# InkTime.net
KiCad netlist of a schematic drawn in EAGLE
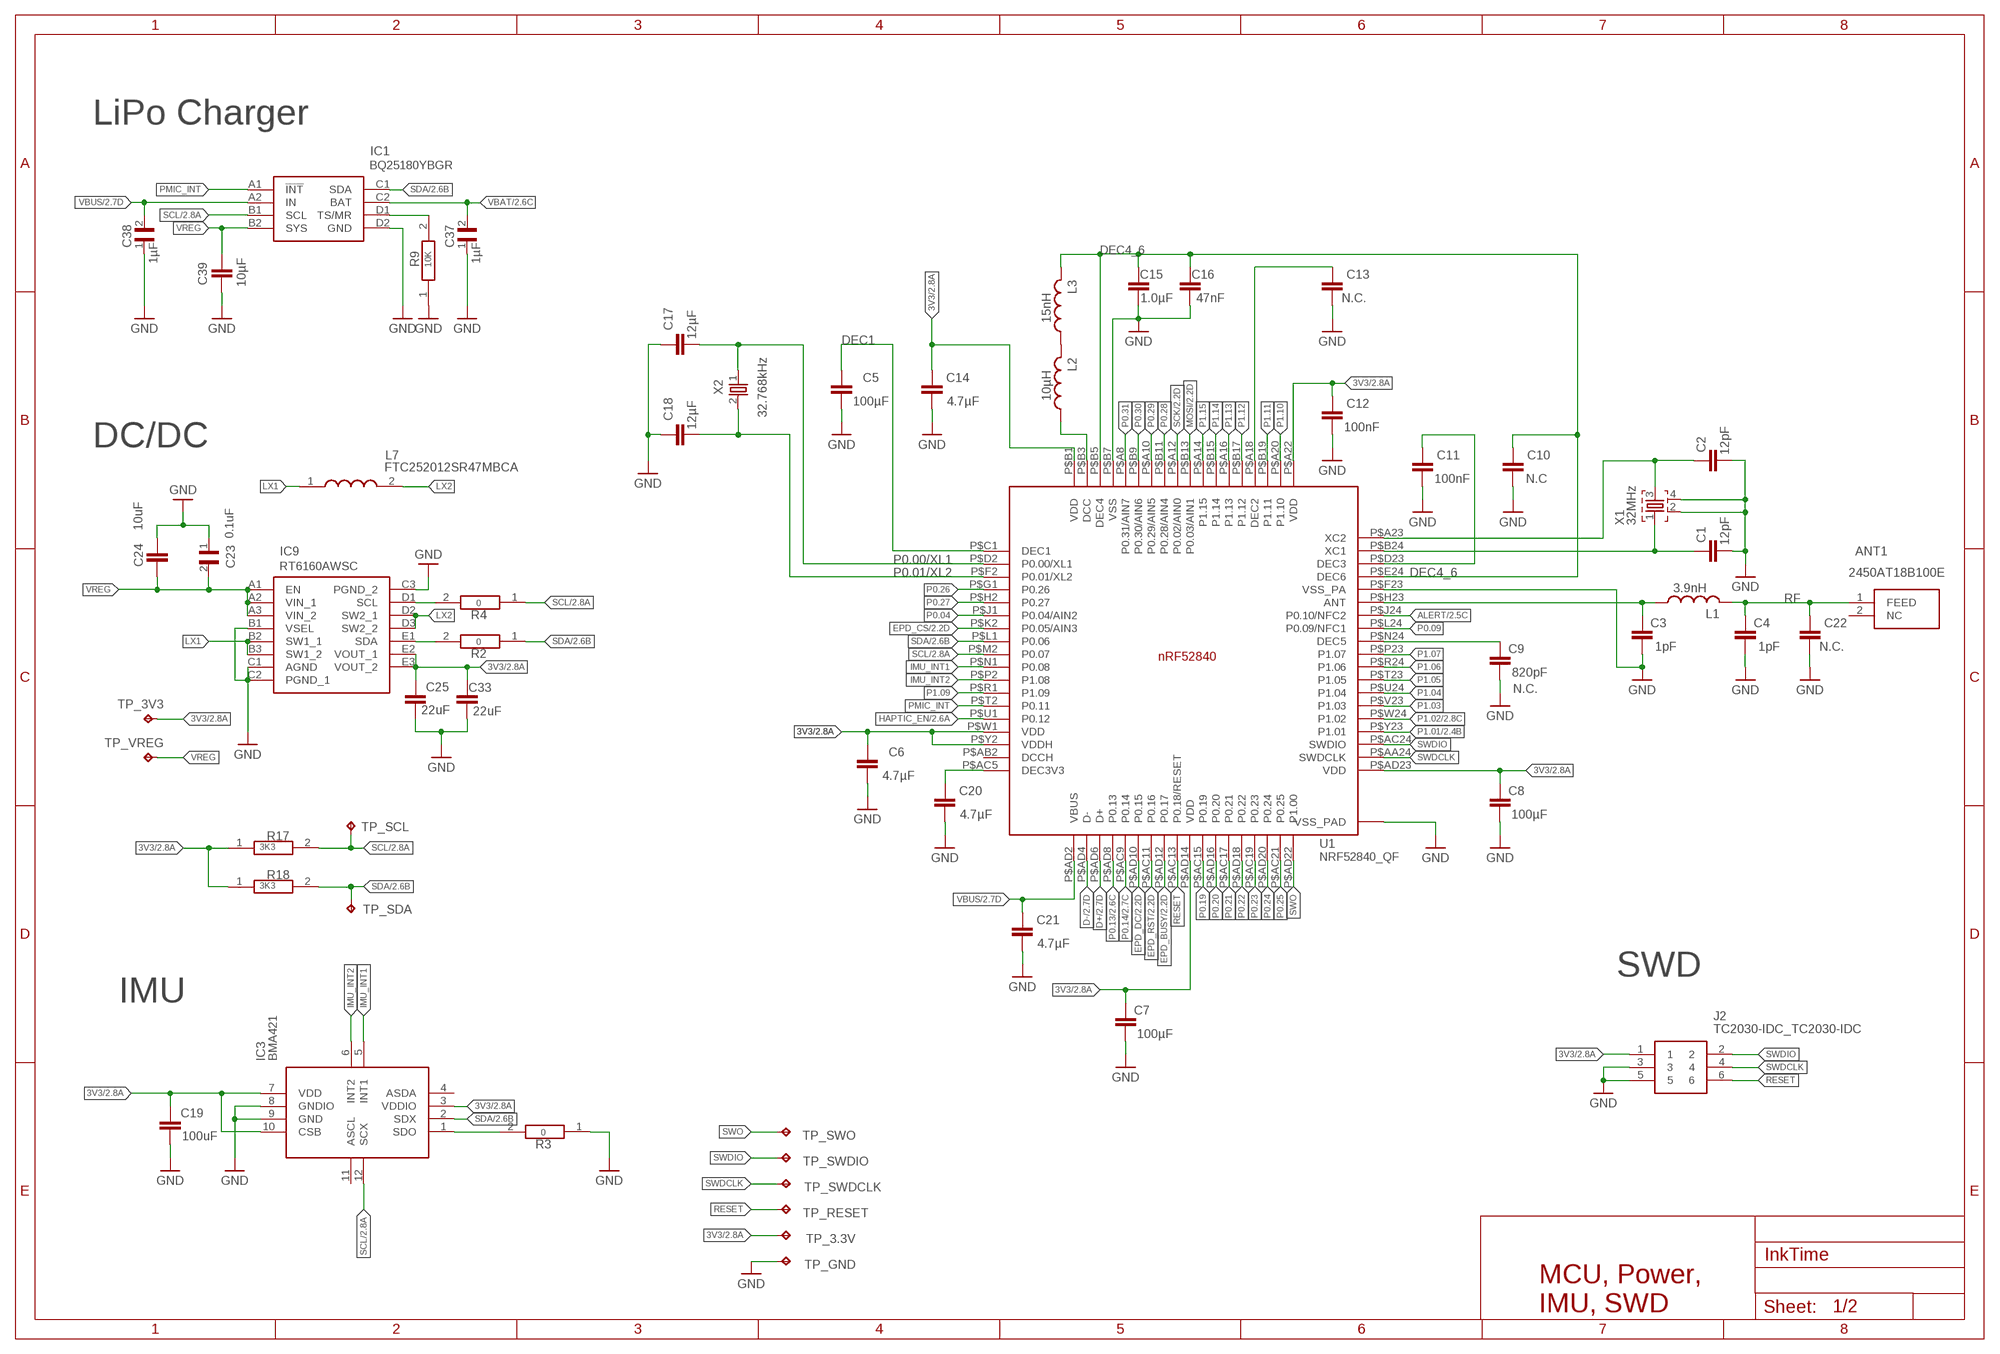
[diagram p0: schematic, sheet 1]
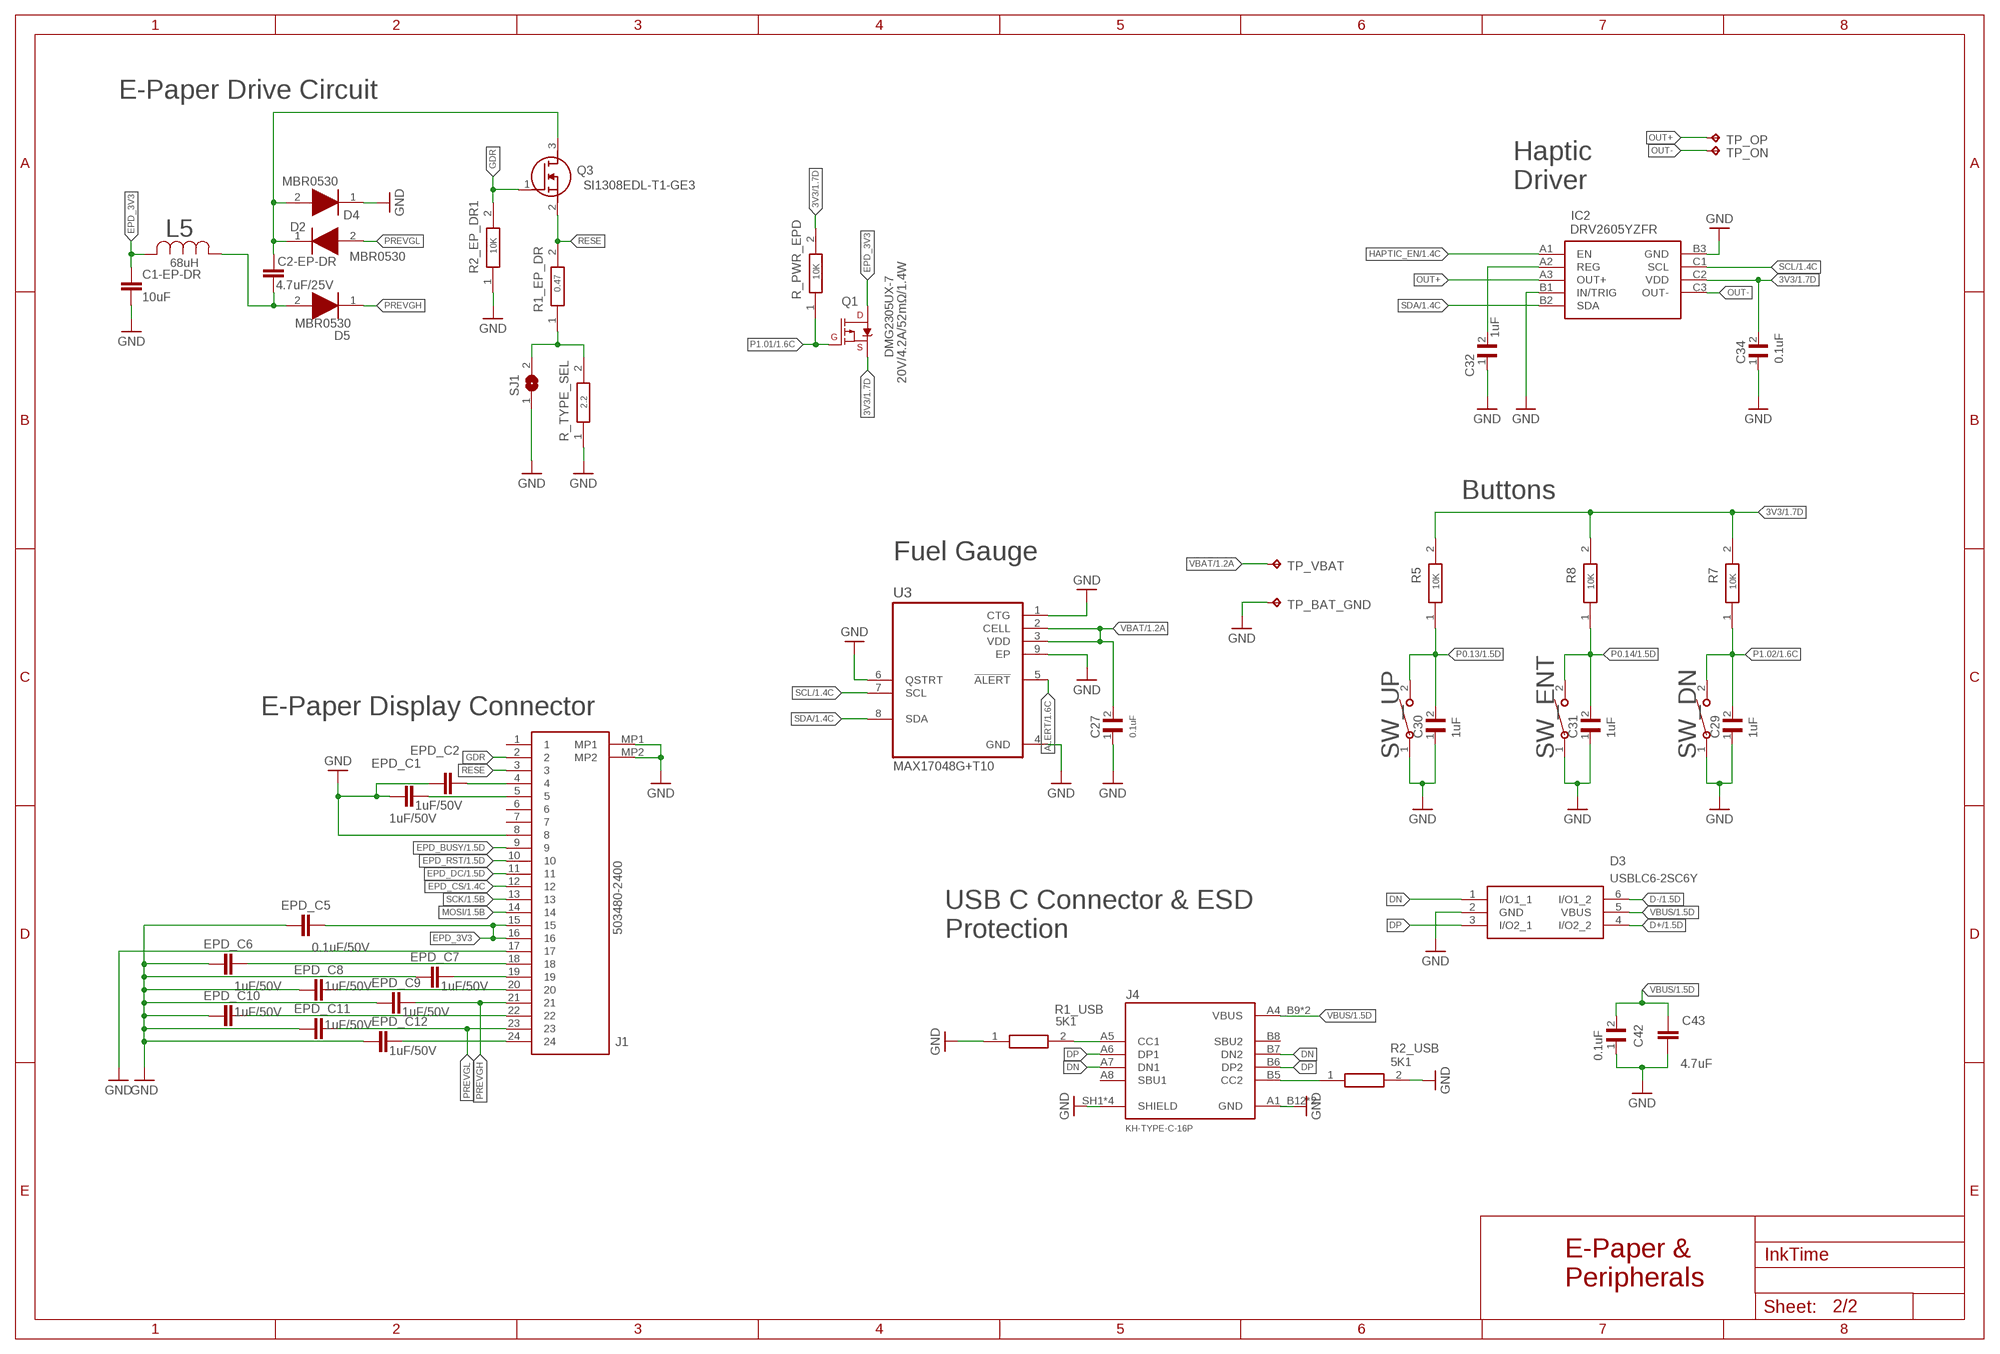
[diagram p1: schematic, sheet 2]

(export (version "E")
  (design (tool "Eeschema 10.0.6"))
  (components
    (comp (ref "ANT1")
      (value "2450AT18B100E_2450AT18B100E")
      (footprint "eagle-import:2450AT18B100E_ANTC3216X140N")
      (fields
        (field (name "ARROW_PART_NUMBER") "2450AT18B100E")
        (field (name "MANUFACTURER_PART_NUMBER") "2450AT18B100E")
        (field (name "MOUSER_PART_NUMBER") "609-2450AT18B100E")
      )
      (libsource (lib "eagle-import") (part "2450AT18B100E_2450AT18B100E"))
    )
    (comp (ref "C1")
      (value "12pF")
      (footprint "eagle-import:NORDIC_NRF_3_RESC0201_L")
      (libsource (lib "eagle-import") (part "NORDIC_NRF_3_CAPACITOR_0201_L"))
    )
    (comp (ref "C2")
      (value "12pF")
      (footprint "eagle-import:NORDIC_NRF_3_RESC0201_L")
      (libsource (lib "eagle-import") (part "NORDIC_NRF_3_CAPACITOR_0201_L"))
    )
    (comp (ref "C3")
      (value "1pF")
      (footprint "eagle-import:NORDIC_NRF_3_RESC0201_L")
      (libsource (lib "eagle-import") (part "NORDIC_NRF_3_CAPACITOR_0201_L"))
    )
    (comp (ref "C4")
      (value "1pF")
      (footprint "eagle-import:NORDIC_NRF_3_RESC0201_L")
      (libsource (lib "eagle-import") (part "NORDIC_NRF_3_CAPACITOR_0201_L"))
    )
    (comp (ref "C5")
      (value "100µF")
      (footprint "eagle-import:NORDIC_NRF_3_RESC0201_L")
      (libsource (lib "eagle-import") (part "NORDIC_NRF_3_CAPACITOR_0201_L"))
    )
    (comp (ref "C6")
      (value "4.7µF")
      (footprint "eagle-import:NORDIC_NRF_3_RESC0201_L")
      (libsource (lib "eagle-import") (part "NORDIC_NRF_3_CAPACITOR_0201_L"))
    )
    (comp (ref "C7")
      (value "100µF")
      (footprint "eagle-import:NORDIC_NRF_3_RESC0201_L")
      (libsource (lib "eagle-import") (part "NORDIC_NRF_3_CAPACITOR_0201_L"))
    )
    (comp (ref "C8")
      (value "100µF")
      (footprint "eagle-import:NORDIC_NRF_3_RESC0201_L")
      (libsource (lib "eagle-import") (part "NORDIC_NRF_3_CAPACITOR_0201_L"))
    )
    (comp (ref "C9")
      (value "820pF")
      (footprint "eagle-import:NORDIC_NRF_3_RESC0201_L")
      (fields (field (name "NO") "N.C."))
      (libsource (lib "eagle-import") (part "NORDIC_NRF_3_CAPACITOR_0201_L"))
    )
    (comp (ref "C10")
      (value "N.C")
      (footprint "eagle-import:NORDIC_NRF_3_RESC0201_L")
      (libsource (lib "eagle-import") (part "NORDIC_NRF_3_CAPACITOR_0201_L"))
    )
    (comp (ref "C11")
      (value "100nF")
      (footprint "eagle-import:NORDIC_NRF_3_RESC0201_L")
      (libsource (lib "eagle-import") (part "NORDIC_NRF_3_CAPACITOR_0201_L"))
    )
    (comp (ref "C12")
      (value "100nF")
      (footprint "eagle-import:NORDIC_NRF_3_RESC0201_L")
      (libsource (lib "eagle-import") (part "NORDIC_NRF_3_CAPACITOR_0201_L"))
    )
    (comp (ref "C13")
      (value "N.C.")
      (footprint "eagle-import:NORDIC_NRF_3_RESC0201_L")
      (libsource (lib "eagle-import") (part "NORDIC_NRF_3_CAPACITOR_0201_L"))
    )
    (comp (ref "C14")
      (value "4.7µF")
      (footprint "eagle-import:NORDIC_NRF_3_RESC0201_L")
      (libsource (lib "eagle-import") (part "NORDIC_NRF_3_CAPACITOR_0201_L"))
    )
    (comp (ref "C15")
      (value "1.0µF")
      (footprint "eagle-import:NORDIC_NRF_3_RESC0201_L")
      (libsource (lib "eagle-import") (part "NORDIC_NRF_3_CAPACITOR_0201_L"))
    )
    (comp (ref "C16")
      (value "47nF")
      (footprint "eagle-import:NORDIC_NRF_3_RESC0201_L")
      (libsource (lib "eagle-import") (part "NORDIC_NRF_3_CAPACITOR_0201_L"))
    )
    (comp (ref "C17")
      (value "12µF")
      (footprint "eagle-import:NORDIC_NRF_3_RESC0201_L")
      (libsource (lib "eagle-import") (part "NORDIC_NRF_3_CAPACITOR_0201_L"))
    )
    (comp (ref "C18")
      (value "12µF")
      (footprint "eagle-import:NORDIC_NRF_3_RESC0201_L")
      (libsource (lib "eagle-import") (part "NORDIC_NRF_3_CAPACITOR_0201_L"))
    )
    (comp (ref "C19")
      (value "100uF")
      (footprint "eagle-import:NORDIC_NRF_3_RESC0201_L")
      (libsource (lib "eagle-import") (part "NORDIC_NRF_3_CAPACITOR_0201_L"))
    )
    (comp (ref "C20")
      (value "4.7µF")
      (footprint "eagle-import:NORDIC_NRF_3_RESC0201_L")
      (libsource (lib "eagle-import") (part "NORDIC_NRF_3_CAPACITOR_0201_L"))
    )
    (comp (ref "C21")
      (value "4.7µF")
      (footprint "eagle-import:NORDIC_NRF_3_RESC0201_L")
      (libsource (lib "eagle-import") (part "NORDIC_NRF_3_CAPACITOR_0201_L"))
    )
    (comp (ref "C22")
      (value "N.C.")
      (footprint "eagle-import:NORDIC_NRF_3_RESC0201_L")
      (libsource (lib "eagle-import") (part "NORDIC_NRF_3_CAPACITOR_0201_L"))
    )
    (comp (ref "C23")
      (value "GRM011R60J152KE01L_2_GRM011R60J152KE01L")
      (footprint "eagle-import:GRM011R60J152KE01L_2_CAPC0201X13N")
      (fields
        (field (name "MF") "Murata")
        (field (name "MP") "GRM011R60J152KE01L")
        (field (name "F") "0.1uF")
      )
      (libsource (lib "eagle-import") (part "GRM011R60J152KE01L_2_GRM011R60J152KE01L"))
    )
    (comp (ref "C24")
      (value "10uF")
      (footprint "eagle-import:NORDIC_NRF_3_RESC0201_L")
      (libsource (lib "eagle-import") (part "NORDIC_NRF_3_CAPACITOR_0201_L"))
    )
    (comp (ref "C25")
      (value "22uF")
      (footprint "eagle-import:NORDIC_NRF_3_RESC0201_L")
      (libsource (lib "eagle-import") (part "NORDIC_NRF_3_CAPACITOR_0201_L"))
    )
    (comp (ref "C33")
      (value "22uF")
      (footprint "eagle-import:NORDIC_NRF_3_RESC0201_L")
      (libsource (lib "eagle-import") (part "NORDIC_NRF_3_CAPACITOR_0201_L"))
    )
    (comp (ref "C37")
      (value "GRM011R60J152KE01L_2_GRM011R60J152KE01L")
      (footprint "eagle-import:GRM011R60J152KE01L_2_CAPC0201X13N")
      (fields (field (name "MF") "Murata") (field (name "MP") "GRM011R60J152KE01L") (field (name "F") "1µF"))
      (libsource (lib "eagle-import") (part "GRM011R60J152KE01L_2_GRM011R60J152KE01L"))
    )
    (comp (ref "C38")
      (value "GRM011R60J152KE01L_2_GRM011R60J152KE01L")
      (footprint "eagle-import:GRM011R60J152KE01L_2_CAPC0201X13N")
      (fields (field (name "MF") "Murata") (field (name "MP") "GRM011R60J152KE01L") (field (name "F") "1µF"))
      (libsource (lib "eagle-import") (part "GRM011R60J152KE01L_2_GRM011R60J152KE01L"))
    )
    (comp (ref "C39")
      (value "10µF")
      (footprint "eagle-import:NORDIC_NRF_3_RESC0201_L")
      (libsource (lib "eagle-import") (part "NORDIC_NRF_3_CAPACITOR_0201_L"))
    )
    (comp (ref "IC1")
      (value "BQ25180YBGR_BQ25180YBGR")
      (footprint "eagle-import:BQ25180YBGR_BGA8C40P2X4_100X155X50")
      (fields
        (field (name "ARROW_PART_NUMBER") "BQ25180YBGR")
        (field (name "MANUFACTURER_PART_NUMBER") "BQ25180YBGR")
        (field (name "MOUSER_PART_NUMBER") "595-BQ25180YBGR")
      )
      (libsource (lib "eagle-import") (part "BQ25180YBGR_BQ25180YBGR"))
    )
    (comp (ref "IC3")
      (value "BMA423_BMA423")
      (footprint "eagle-import:BMA423_BMA423")
      (fields
        (field (name "ARROW_PART_NUMBER") "BMA423")
        (field (name "MANUFACTURER_PART_NUMBER") "BMA423")
        (field (name "MOUSER_PART_NUMBER") "262-BMA423")
        (field (name "ARROW_PART_NUMBER_1") "BMA421")
      )
      (libsource (lib "eagle-import") (part "BMA423_BMA423"))
    )
    (comp (ref "IC9")
      (value "RT6160AWSC_RT6160AWSC")
      (footprint "eagle-import:RT6160AWSC_BGA15C40P3X5_140X230X60")
      (fields
        (field (name "MANUFACTURER_PART_NUMBER") "RT6160AWSC")
        (field (name "MOUSER_PART_NUMBER") "835-RT6160AWSC")
      )
      (libsource (lib "eagle-import") (part "RT6160AWSC_RT6160AWSC"))
    )
    (comp (ref "J2")
      (value "TC2030-IDC_TC2030-IDC")
      (footprint "eagle-import:TC2030-IDC_TC2030IDC")
      (fields (field (name "MANUFACTURER_PART_NUMBER") "TC2030-IDC"))
      (libsource (lib "eagle-import") (part "TC2030-IDC_TC2030-IDC"))
    )
    (comp (ref "L1")
      (value "3.9nH")
      (footprint "eagle-import:NORDIC_NRF_2_RESC0402_L")
      (libsource (lib "eagle-import") (part "NORDIC_NRF_2_INDUCTOR_0402_L"))
    )
    (comp (ref "L2")
      (value "10µH")
      (footprint "eagle-import:NORDIC_NRF_2_RESC0402_L")
      (libsource (lib "eagle-import") (part "NORDIC_NRF_2_INDUCTOR_0402_L"))
    )
    (comp (ref "L3")
      (value "15nH")
      (footprint "eagle-import:NORDIC_NRF_2_RESC0402_L")
      (libsource (lib "eagle-import") (part "NORDIC_NRF_2_INDUCTOR_0402_L"))
    )
    (comp (ref "L7")
      (value "MLP2016SR47MT0S1_FTC252012SR47MBCA")
      (footprint "eagle-import:MLP2016SR47MT0S1_INDC2016X100N")
      (fields
        (field (name "MANUFACTURER_PART_NUMBER") "FTC252012SR47MBCA")
        (field (name "N") "FTC252012SR47MBCA")
      )
      (libsource (lib "eagle-import") (part "MLP2016SR47MT0S1_FTC252012SR47MBCA"))
    )
    (comp (ref "R2")
      (value "ERA-1AEB3401C_CPF0201D7K68C1")
      (footprint "eagle-import:ERA-1AEB3401C_0201")
      (fields (field (name "R") "0"))
      (libsource (lib "eagle-import") (part "ERA-1AEB3401C_CPF0201D7K68C1"))
    )
    (comp (ref "R3")
      (value "ERA-1AEB3401C_CPF0201D7K68C1")
      (footprint "eagle-import:ERA-1AEB3401C_0201")
      (fields (field (name "R") "0"))
      (libsource (lib "eagle-import") (part "ERA-1AEB3401C_CPF0201D7K68C1"))
    )
    (comp (ref "R4")
      (value "ERA-1AEB3401C_CPF0201D7K68C1")
      (footprint "eagle-import:ERA-1AEB3401C_0201")
      (fields (field (name "R") "0"))
      (libsource (lib "eagle-import") (part "ERA-1AEB3401C_CPF0201D7K68C1"))
    )
    (comp (ref "R9")
      (value "ERA-1AEB3401C_CPF0201D7K68C1")
      (footprint "eagle-import:ERA-1AEB3401C_0201")
      (fields (field (name "R") "10K"))
      (libsource (lib "eagle-import") (part "ERA-1AEB3401C_CPF0201D7K68C1"))
    )
    (comp (ref "R17")
      (value "ERA-1AEB3401C_CPF0201D7K68C1")
      (footprint "eagle-import:ERA-1AEB3401C_0201")
      (fields (field (name "R") "3K3"))
      (libsource (lib "eagle-import") (part "ERA-1AEB3401C_CPF0201D7K68C1"))
    )
    (comp (ref "R18")
      (value "ERA-1AEB3401C_CPF0201D7K68C1")
      (footprint "eagle-import:ERA-1AEB3401C_0201")
      (fields (field (name "R") "3K3"))
      (libsource (lib "eagle-import") (part "ERA-1AEB3401C_CPF0201D7K68C1"))
    )
    (comp (ref "TP_3.3V")
      (value "HECTOR_WATCH_1_TPTP20R")
      (footprint "eagle-import:HECTOR_WATCH_1_TP20R")
      (libsource (lib "eagle-import") (part "HECTOR_WATCH_1_TPTP20R"))
    )
    (comp (ref "TP_3V3")
      (value "HECTOR_WATCH_1_TPTP20R")
      (footprint "eagle-import:HECTOR_WATCH_1_TP20R")
      (libsource (lib "eagle-import") (part "HECTOR_WATCH_1_TPTP20R"))
    )
    (comp (ref "TP_GND")
      (value "HECTOR_WATCH_1_TPTP20R")
      (footprint "eagle-import:HECTOR_WATCH_1_TP20R")
      (libsource (lib "eagle-import") (part "HECTOR_WATCH_1_TPTP20R"))
    )
    (comp (ref "TP_RESET")
      (value "HECTOR_WATCH_1_TPTP20R")
      (footprint "eagle-import:HECTOR_WATCH_1_TP20R")
      (libsource (lib "eagle-import") (part "HECTOR_WATCH_1_TPTP20R"))
    )
    (comp (ref "TP_SCL")
      (value "HECTOR_WATCH_1_TPTP20R")
      (footprint "eagle-import:HECTOR_WATCH_1_TP20R")
      (libsource (lib "eagle-import") (part "HECTOR_WATCH_1_TPTP20R"))
    )
    (comp (ref "TP_SDA")
      (value "HECTOR_WATCH_1_TPTP20R")
      (footprint "eagle-import:HECTOR_WATCH_1_TP20R")
      (libsource (lib "eagle-import") (part "HECTOR_WATCH_1_TPTP20R"))
    )
    (comp (ref "TP_SWDCLK")
      (value "HECTOR_WATCH_1_TPTP20R")
      (footprint "eagle-import:HECTOR_WATCH_1_TP20R")
      (libsource (lib "eagle-import") (part "HECTOR_WATCH_1_TPTP20R"))
    )
    (comp (ref "TP_SWDIO")
      (value "HECTOR_WATCH_1_TPTP20R")
      (footprint "eagle-import:HECTOR_WATCH_1_TP20R")
      (libsource (lib "eagle-import") (part "HECTOR_WATCH_1_TPTP20R"))
    )
    (comp (ref "TP_SWO")
      (value "HECTOR_WATCH_1_TPTP20R")
      (footprint "eagle-import:HECTOR_WATCH_1_TP20R")
      (libsource (lib "eagle-import") (part "HECTOR_WATCH_1_TPTP20R"))
    )
    (comp (ref "TP_VREG")
      (value "HECTOR_WATCH_1_TPTP20R")
      (footprint "eagle-import:HECTOR_WATCH_1_TP20R")
      (libsource (lib "eagle-import") (part "HECTOR_WATCH_1_TPTP20R"))
    )
    (comp (ref "U1")
      (value "NORDIC_NRF_4_NRF52840_QF")
      (footprint "eagle-import:NORDIC_NRF_4_AQFN50P700X700X85_HS-74N")
      (fields (field (name "NU") "NRF52840_QF"))
      (libsource (lib "eagle-import") (part "NORDIC_NRF_4_NRF52840_QF"))
    )
    (comp (ref "X1")
      (value "32MHz")
      (footprint "eagle-import:NORDIC_NRF_BT-XTAL_2016_N")
      (libsource (lib "eagle-import") (part "NORDIC_NRF_XTAL_32MHZ"))
    )
    (comp (ref "X2")
      (value "32.768kHz")
      (footprint "eagle-import:NORDIC_NRF_1_XTAL_3215_N")
      (libsource (lib "eagle-import") (part "NORDIC_NRF_1_XTAL_32KHZ"))
    )
    (comp (ref "C1-EP-DR")
      (value "10uF")
      (footprint "eagle-import:NORDIC_NRF_3_RESC0201_L")
      (libsource (lib "eagle-import") (part "NORDIC_NRF_3_CAPACITOR_0201_L"))
    )
    (comp (ref "C2-EP-DR")
      (value "4.7uF/25V")
      (footprint "eagle-import:NORDIC_NRF_3_RESC0201_L")
      (libsource (lib "eagle-import") (part "NORDIC_NRF_3_CAPACITOR_0201_L"))
    )
    (comp (ref "C27")
      (value "GRM011R60J152KE01L_2_GRM011R60J152KE01L")
      (footprint "eagle-import:GRM011R60J152KE01L_2_CAPC0201X13N")
      (fields
        (field (name "MF") "Murata")
        (field (name "MP") "GRM011R60J152KE01L")
        (field (name "F") "0.1uF")
      )
      (libsource (lib "eagle-import") (part "GRM011R60J152KE01L_2_GRM011R60J152KE01L"))
    )
    (comp (ref "C29")
      (value "GRM011R60J152KE01L_2_GRM011R60J152KE01L")
      (footprint "eagle-import:GRM011R60J152KE01L_2_CAPC0201X13N")
      (fields (field (name "MF") "Murata") (field (name "MP") "GRM011R60J152KE01L") (field (name "F") "1uF"))
      (libsource (lib "eagle-import") (part "GRM011R60J152KE01L_2_GRM011R60J152KE01L"))
    )
    (comp (ref "C30")
      (value "GRM011R60J152KE01L_2_GRM011R60J152KE01L")
      (footprint "eagle-import:GRM011R60J152KE01L_2_CAPC0201X13N")
      (fields (field (name "MF") "Murata") (field (name "MP") "GRM011R60J152KE01L") (field (name "F") "1uF"))
      (libsource (lib "eagle-import") (part "GRM011R60J152KE01L_2_GRM011R60J152KE01L"))
    )
    (comp (ref "C31")
      (value "GRM011R60J152KE01L_2_GRM011R60J152KE01L")
      (footprint "eagle-import:GRM011R60J152KE01L_2_CAPC0201X13N")
      (fields (field (name "MF") "Murata") (field (name "MP") "GRM011R60J152KE01L") (field (name "F") "1uF"))
      (libsource (lib "eagle-import") (part "GRM011R60J152KE01L_2_GRM011R60J152KE01L"))
    )
    (comp (ref "C32")
      (value "GRM011R60J152KE01L_2_GRM011R60J152KE01L")
      (footprint "eagle-import:GRM011R60J152KE01L_2_CAPC0201X13N")
      (fields (field (name "MF") "Murata") (field (name "MP") "GRM011R60J152KE01L") (field (name "F") "1uF"))
      (libsource (lib "eagle-import") (part "GRM011R60J152KE01L_2_GRM011R60J152KE01L"))
    )
    (comp (ref "C34")
      (value "GRM011R60J152KE01L_2_GRM011R60J152KE01L")
      (footprint "eagle-import:GRM011R60J152KE01L_2_CAPC0201X13N")
      (fields
        (field (name "MF") "Murata")
        (field (name "MP") "GRM011R60J152KE01L")
        (field (name "F") "0.1uF")
      )
      (libsource (lib "eagle-import") (part "GRM011R60J152KE01L_2_GRM011R60J152KE01L"))
    )
    (comp (ref "C42")
      (value "GRM011R60J152KE01L_2_GRM011R60J152KE01L")
      (footprint "eagle-import:GRM011R60J152KE01L_2_CAPC0201X13N")
      (fields
        (field (name "MF") "Murata")
        (field (name "MP") "GRM011R60J152KE01L")
        (field (name "F") "0.1uF")
      )
      (libsource (lib "eagle-import") (part "GRM011R60J152KE01L_2_GRM011R60J152KE01L"))
    )
    (comp (ref "C43")
      (value "4.7uF")
      (footprint "eagle-import:NORDIC_NRF_3_RESC0201_L")
      (libsource (lib "eagle-import") (part "NORDIC_NRF_3_CAPACITOR_0201_L"))
    )
    (comp (ref "D2")
      (value "ESP32_C6_LIBRARY_5_MBR0530")
      (footprint "eagle-import:ESP32_C6_LIBRARY_5_SOD3716X135N")
      (fields (field (name "MF") "ON Semiconductor") (field (name "MP") "MBR0530"))
      (libsource (lib "eagle-import") (part "ESP32_C6_LIBRARY_5_MBR0530"))
    )
    (comp (ref "D3")
      (value "ESP32_C6_LIBRARY_3_USBLC6-2SC6Y")
      (footprint "eagle-import:ESP32_C6_LIBRARY_3_SOT95P280X145-6N")
      (fields (field (name "MF") "STMicroelectronics") (field (name "MP") "USBLC6-2SC6Y"))
      (libsource (lib "eagle-import") (part "ESP32_C6_LIBRARY_3_USBLC6-2SC6Y"))
    )
    (comp (ref "D4")
      (value "ESP32_C6_LIBRARY_5_MBR0530")
      (footprint "eagle-import:ESP32_C6_LIBRARY_5_SOD3716X135N")
      (fields (field (name "MF") "ON Semiconductor") (field (name "MP") "MBR0530"))
      (libsource (lib "eagle-import") (part "ESP32_C6_LIBRARY_5_MBR0530"))
    )
    (comp (ref "D5")
      (value "ESP32_C6_LIBRARY_5_MBR0530")
      (footprint "eagle-import:ESP32_C6_LIBRARY_5_SOD3716X135N")
      (fields (field (name "MF") "ON Semiconductor") (field (name "MP") "MBR0530"))
      (libsource (lib "eagle-import") (part "ESP32_C6_LIBRARY_5_MBR0530"))
    )
    (comp (ref "EPD_C1")
      (value "1uF/50V")
      (footprint "eagle-import:NORDIC_NRF_3_RESC0201_L")
      (libsource (lib "eagle-import") (part "NORDIC_NRF_3_CAPACITOR_0201_L"))
    )
    (comp (ref "EPD_C2")
      (value "1uF/50V")
      (footprint "eagle-import:NORDIC_NRF_3_RESC0201_L")
      (libsource (lib "eagle-import") (part "NORDIC_NRF_3_CAPACITOR_0201_L"))
    )
    (comp (ref "EPD_C5")
      (value "0.1uF/50V")
      (footprint "eagle-import:NORDIC_NRF_3_RESC0201_L")
      (libsource (lib "eagle-import") (part "NORDIC_NRF_3_CAPACITOR_0201_L"))
    )
    (comp (ref "EPD_C6")
      (value "1uF/50V")
      (footprint "eagle-import:NORDIC_NRF_3_RESC0201_L")
      (libsource (lib "eagle-import") (part "NORDIC_NRF_3_CAPACITOR_0201_L"))
    )
    (comp (ref "EPD_C7")
      (value "1uF/50V")
      (footprint "eagle-import:NORDIC_NRF_3_RESC0201_L")
      (libsource (lib "eagle-import") (part "NORDIC_NRF_3_CAPACITOR_0201_L"))
    )
    (comp (ref "EPD_C8")
      (value "1uF/50V")
      (footprint "eagle-import:NORDIC_NRF_3_RESC0201_L")
      (libsource (lib "eagle-import") (part "NORDIC_NRF_3_CAPACITOR_0201_L"))
    )
    (comp (ref "EPD_C9")
      (value "1uF/50V")
      (footprint "eagle-import:NORDIC_NRF_3_RESC0201_L")
      (libsource (lib "eagle-import") (part "NORDIC_NRF_3_CAPACITOR_0201_L"))
    )
    (comp (ref "EPD_C10")
      (value "1uF/50V")
      (footprint "eagle-import:NORDIC_NRF_3_RESC0201_L")
      (libsource (lib "eagle-import") (part "NORDIC_NRF_3_CAPACITOR_0201_L"))
    )
    (comp (ref "EPD_C11")
      (value "1uF/50V")
      (footprint "eagle-import:NORDIC_NRF_3_RESC0201_L")
      (libsource (lib "eagle-import") (part "NORDIC_NRF_3_CAPACITOR_0201_L"))
    )
    (comp (ref "EPD_C12")
      (value "1uF/50V")
      (footprint "eagle-import:NORDIC_NRF_3_RESC0201_L")
      (libsource (lib "eagle-import") (part "NORDIC_NRF_3_CAPACITOR_0201_L"))
    )
    (comp (ref "IC2")
      (value "DRV2605YZFR_DRV2605YZFR")
      (footprint "eagle-import:DRV2605YZFR_BGA9C50P3X3_144X144X62")
      (fields
        (field (name "ARROW_PART_NUMBER") "DRV2605YZFR")
        (field (name "MANUFACTURER_PART_NUMBER") "DRV2605YZFR")
      )
      (libsource (lib "eagle-import") (part "DRV2605YZFR_DRV2605YZFR"))
    )
    (comp (ref "J1")
      (value "503480-2400_503480-2400")
      (footprint "eagle-import:503480-2400_5034802400")
      (fields
        (field (name "MANUFACTURER_PART_NUMBER") "503480-2400")
        (field (name "MOUSER_PART_NUMBER") "538-503480-2400")
      )
      (libsource (lib "eagle-import") (part "503480-2400_503480-2400"))
    )
    (comp (ref "J4")
      (value "KH-TYPE-C-16P_KH-TYPE-C-16P")
      (footprint "eagle-import:KH-TYPE-C-16P_KINGHELM_KH-TYPE-C-16P")
      (fields (field (name "MF") "kinghelm") (field (name "MP") "KH-TYPE-C-16P"))
      (libsource (lib "eagle-import") (part "KH-TYPE-C-16P_KH-TYPE-C-16P"))
    )
    (comp (ref "L5")
      (value "ESP32_C6_LIBRARY_2_744043680IND_4828-WE-TPC_WRE")
      (footprint "eagle-import:ESP32_C6_LIBRARY_2_IND_4828-WE-TPC_WRE")
      (fields
        (field (name "MANUFACTURER_PART_NUMBER") "744043680")
        (field (name "ATR") "68uH")
        (field (name "COPYRIGHT") "Copyright (C) 2024 Ultra Librarian. All rights reserved.")
      )
      (libsource (lib "eagle-import") (part "ESP32_C6_LIBRARY_2_744043680IND_4828-WE-TPC_WRE"))
    )
    (comp (ref "Q1")
      (value "20V/4.2A/52mΩ/1.4W")
      (footprint "eagle-import:ESP32_C6_LIBRARY_4_ESP32_C6_LIBRARY_4_ESP32_C6_LIBRARY_4_ESP32_C6_LIBRARY_4_ESP32_WROVER_SPARKFUN-DISCRETESEMI_SOT23-3")
      (fields (field (name "NAM") "DMG2305UX-7 "))
      (libsource (lib "eagle-import") (part "ESP32_C6_LIBRARY_4_ESP32_WROVER_SPARKFUN-DISCRETESEMI_MOSFET_PCH-DMG2305UX-7"))
    )
    (comp (ref "Q3")
      (value "ESP32_C6_LIBRARY_6_SI1308EDL-T1-GE3")
      (footprint "eagle-import:ESP32_C6_LIBRARY_6_SOT65P210X110-3N")
      (fields (field (name "MF") "Vishay Siliconix") (field (name "MP") "SI1308EDL-T1-GE3"))
      (libsource (lib "eagle-import") (part "ESP32_C6_LIBRARY_6_SI1308EDL-T1-GE3"))
    )
    (comp (ref "R1_EP_DR")
      (value "ERA-1AEB3401C_CPF0201D7K68C1")
      (footprint "eagle-import:ERA-1AEB3401C_0201")
      (fields (field (name "ATR") "0.47"))
      (libsource (lib "eagle-import") (part "ERA-1AEB3401C_CPF0201D7K68C1"))
    )
    (comp (ref "R1_USB")
      (value "ERA-1AEB3401C_CPF0201D7K68C1")
      (footprint "eagle-import:ERA-1AEB3401C_0201")
      (fields (field (name "ATR") "5K1"))
      (libsource (lib "eagle-import") (part "ERA-1AEB3401C_CPF0201D7K68C1"))
    )
    (comp (ref "R2_EP_DR1")
      (value "ERA-1AEB3401C_CPF0201D7K68C1")
      (footprint "eagle-import:ERA-1AEB3401C_0201")
      (fields (field (name "ATR") "10K"))
      (libsource (lib "eagle-import") (part "ERA-1AEB3401C_CPF0201D7K68C1"))
    )
    (comp (ref "R2_USB")
      (value "ERA-1AEB3401C_CPF0201D7K68C1")
      (footprint "eagle-import:ERA-1AEB3401C_0201")
      (fields (field (name "ATR") "5K1"))
      (libsource (lib "eagle-import") (part "ERA-1AEB3401C_CPF0201D7K68C1"))
    )
    (comp (ref "R5")
      (value "ERA-1AEB3401C_CPF0201D7K68C1")
      (footprint "eagle-import:ERA-1AEB3401C_0201")
      (fields (field (name "ATR") "10K"))
      (libsource (lib "eagle-import") (part "ERA-1AEB3401C_CPF0201D7K68C1"))
    )
    (comp (ref "R7")
      (value "ERA-1AEB3401C_CPF0201D7K68C1")
      (footprint "eagle-import:ERA-1AEB3401C_0201")
      (fields (field (name "ATR") "10K"))
      (libsource (lib "eagle-import") (part "ERA-1AEB3401C_CPF0201D7K68C1"))
    )
    (comp (ref "R8")
      (value "ERA-1AEB3401C_CPF0201D7K68C1")
      (footprint "eagle-import:ERA-1AEB3401C_0201")
      (fields (field (name "ATR") "10K"))
      (libsource (lib "eagle-import") (part "ERA-1AEB3401C_CPF0201D7K68C1"))
    )
    (comp (ref "R_PWR_EPD")
      (value "ERA-1AEB3401C_CPF0201D7K68C1")
      (footprint "eagle-import:ERA-1AEB3401C_0201")
      (fields (field (name "ATR") "10K"))
      (libsource (lib "eagle-import") (part "ERA-1AEB3401C_CPF0201D7K68C1"))
    )
    (comp (ref "R_TYPE_SEL")
      (value "ERA-1AEB3401C_CPF0201D7K68C1")
      (footprint "eagle-import:ERA-1AEB3401C_0201")
      (fields (field (name "ATR") "2.2"))
      (libsource (lib "eagle-import") (part "ERA-1AEB3401C_CPF0201D7K68C1"))
    )
    (comp (ref "SJ1")
      (value "ESP32_C6_LIBRARY_7_JUMPER_SJ")
      (footprint "eagle-import:ESP32_C6_LIBRARY_7_JUMPER_SJ")
      (libsource (lib "eagle-import") (part "ESP32_C6_LIBRARY_7_JUMPER_SJ"))
    )
    (comp (ref "SW_DN")
      (value "2025-10-22_07-23-44_LIBRARY_EVP-AKE31ASW_EVP-AKE31A_PAN")
      (footprint "eagle-import:2025-10-22_07-23-44_LIBRARY_SW_EVP-AKE31A_PAN")
      (fields
        (field (name "MANUFACTURER_PART_NUMBER") "EVP-AKE31A")
        (field (name "COPYRIGHT") "Copyright (C) 2025 Ultra Librarian. All rights reserved.")
      )
      (libsource (lib "eagle-import") (part "2025-10-22_07-23-44_LIBRARY_EVP-AKE31ASW_EVP-AKE31A_PAN"))
    )
    (comp (ref "SW_ENT")
      (value "2025-10-22_07-23-44_LIBRARY_EVP-AKE31ASW_EVP-AKE31A_PAN")
      (footprint "eagle-import:2025-10-22_07-23-44_LIBRARY_SW_EVP-AKE31A_PAN")
      (fields
        (field (name "MANUFACTURER_PART_NUMBER") "EVP-AKE31A")
        (field (name "COPYRIGHT") "Copyright (C) 2025 Ultra Librarian. All rights reserved.")
      )
      (libsource (lib "eagle-import") (part "2025-10-22_07-23-44_LIBRARY_EVP-AKE31ASW_EVP-AKE31A_PAN"))
    )
    (comp (ref "SW_UP")
      (value "2025-10-22_07-23-44_LIBRARY_EVP-AKE31ASW_EVP-AKE31A_PAN")
      (footprint "eagle-import:2025-10-22_07-23-44_LIBRARY_SW_EVP-AKE31A_PAN")
      (fields
        (field (name "MANUFACTURER_PART_NUMBER") "EVP-AKE31A")
        (field (name "COPYRIGHT") "Copyright (C) 2025 Ultra Librarian. All rights reserved.")
      )
      (libsource (lib "eagle-import") (part "2025-10-22_07-23-44_LIBRARY_EVP-AKE31ASW_EVP-AKE31A_PAN"))
    )
    (comp (ref "TP_BAT_GND")
      (value "HECTOR_WATCH_1_TPTP20R")
      (footprint "eagle-import:HECTOR_WATCH_1_TP20R")
      (libsource (lib "eagle-import") (part "HECTOR_WATCH_1_TPTP20R"))
    )
    (comp (ref "TP_ON")
      (value "HECTOR_WATCH_1_TPTP20R")
      (footprint "eagle-import:HECTOR_WATCH_1_TP20R")
      (libsource (lib "eagle-import") (part "HECTOR_WATCH_1_TPTP20R"))
    )
    (comp (ref "TP_OP")
      (value "HECTOR_WATCH_1_TPTP20R")
      (footprint "eagle-import:HECTOR_WATCH_1_TP20R")
      (libsource (lib "eagle-import") (part "HECTOR_WATCH_1_TPTP20R"))
    )
    (comp (ref "TP_VBAT")
      (value "HECTOR_WATCH_1_TPTP20R")
      (footprint "eagle-import:HECTOR_WATCH_1_TP20R")
      (libsource (lib "eagle-import") (part "HECTOR_WATCH_1_TPTP20R"))
    )
    (comp (ref "U3")
      (value "ESP32_C6_LIBRARY_MAX17048G+T10")
      (footprint "eagle-import:ESP32_C6_LIBRARY_SON50P200X200X80-9N")
      (fields (field (name "MF") "Analog Devices") (field (name "MP") "MAX17048G+T10"))
      (libsource (lib "eagle-import") (part "ESP32_C6_LIBRARY_MAX17048G+T10"))
    )
  )
  (nets
    (net (code "1") (name "3V3") (class "Default")
      (node (ref "C12") (pin "1") (pinfunction "1_1") (pintype "passive"))
      (node (ref "C14") (pin "1") (pinfunction "1_1") (pintype "passive"))
      (node (ref "C19") (pin "1") (pinfunction "1_1") (pintype "passive"))
      (node (ref "C25") (pin "1") (pinfunction "1_1") (pintype "passive"))
      (node (ref "C33") (pin "1") (pinfunction "1_1") (pintype "passive"))
      (node (ref "C34") (pin "2") (pinfunction "2_2") (pintype "passive"))
      (node (ref "C6") (pin "1") (pinfunction "1_1") (pintype "passive"))
      (node (ref "C7") (pin "1") (pinfunction "1_1") (pintype "passive"))
      (node (ref "C8") (pin "1") (pinfunction "1_1") (pintype "passive"))
      (node (ref "IC2") (pin "C2") (pinfunction "VDD_C2") (pintype "bidirectional"))
      (node (ref "IC3") (pin "10") (pinfunction "CSB_10") (pintype "bidirectional"))
      (node (ref "IC3") (pin "3") (pinfunction "VDDIO_3") (pintype "bidirectional"))
      (node (ref "IC3") (pin "7") (pinfunction "VDD_7") (pintype "bidirectional"))
      (node (ref "IC9") (pin "E2") (pinfunction "VOUT_1_E2") (pintype "bidirectional"))
      (node (ref "IC9") (pin "E3") (pinfunction "VOUT_2_E3") (pintype "bidirectional"))
      (node (ref "J2") (pin "1") (pinfunction "1_1") (pintype "bidirectional"))
      (node (ref "Q1") (pin "2") (pinfunction "S_2") (pintype "bidirectional"))
      (node (ref "R17") (pin "1") (pinfunction "1_1") (pintype "bidirectional"))
      (node (ref "R18") (pin "1") (pinfunction "1_1") (pintype "bidirectional"))
      (node (ref "R_PWR_EPD") (pin "2") (pinfunction "2_2") (pintype "bidirectional"))
      (node (ref "TP_3.3V") (pin "TP") (pinfunction "TP_TP") (pintype "input"))
      (node (ref "TP_3V3") (pin "TP") (pinfunction "TP_TP") (pintype "input"))
      (node (ref "U1") (pin "P$A22") (pinfunction "VDD_P$A22") (pintype "power_in"))
      (node (ref "U1") (pin "P$AD14") (pinfunction "VDD_P$AD14") (pintype "power_in"))
      (node (ref "U1") (pin "P$AD23") (pinfunction "VDD_P$AD23") (pintype "power_in"))
      (node (ref "U1") (pin "P$B1") (pinfunction "VDD_P$B1") (pintype "power_in"))
      (node (ref "U1") (pin "P$W1") (pinfunction "VDD_P$W1") (pintype "power_in"))
      (node (ref "U1") (pin "P$Y2") (pinfunction "VDDH_P$Y2") (pintype "power_in"))
    )
    (net (code "2") (name "3V3{slash}1.7D") (class "Default")
      (node (ref "R5") (pin "2") (pinfunction "2_2") (pintype "bidirectional"))
      (node (ref "R7") (pin "2") (pinfunction "2_2") (pintype "bidirectional"))
      (node (ref "R8") (pin "2") (pinfunction "2_2") (pintype "bidirectional"))
    )
    (net (code "3") (name "ALERT") (class "Default")
      (node (ref "U1") (pin "P$J24") (pinfunction "P0.10/NFC2_P$J24") (pintype "bidirectional"))
      (node (ref "U3") (pin "5") (pinfunction "~{ALERT}_5") (pintype "output"))
    )
    (net (code "4") (name "D+") (class "Default")
      (node (ref "D3") (pin "4") (pinfunction "I/O2_2_4") (pintype "bidirectional"))
      (node (ref "U1") (pin "P$AD6") (pinfunction "D+_P$AD6") (pintype "bidirectional"))
    )
    (net (code "5") (name "D-") (class "Default")
      (node (ref "D3") (pin "6") (pinfunction "I/O1_2_6") (pintype "bidirectional"))
      (node (ref "U1") (pin "P$AD4") (pinfunction "D-_P$AD4") (pintype "bidirectional"))
    )
    (net (code "6") (name "DEC1") (class "Default")
      (node (ref "C5") (pin "1") (pinfunction "1_1") (pintype "passive"))
      (node (ref "U1") (pin "P$C1") (pinfunction "DEC1_P$C1") (pintype "power_in"))
    )
    (net (code "7") (name "DEC4_6") (class "Default")
      (node (ref "C10") (pin "1") (pinfunction "1_1") (pintype "passive"))
      (node (ref "C15") (pin "1") (pinfunction "1_1") (pintype "passive"))
      (node (ref "C16") (pin "1") (pinfunction "1_1") (pintype "passive"))
      (node (ref "L3") (pin "2") (pinfunction "2_2") (pintype "passive"))
      (node (ref "U1") (pin "P$B5") (pinfunction "DEC4_P$B5") (pintype "power_in"))
      (node (ref "U1") (pin "P$E24") (pinfunction "DEC6_P$E24") (pintype "bidirectional"))
    )
    (net (code "8") (name "DN") (class "Default")
      (node (ref "D3") (pin "1") (pinfunction "I/O1_1_1") (pintype "bidirectional"))
      (node (ref "J4") (pin "A7") (pinfunction "DN1_A7") (pintype "bidirectional"))
      (node (ref "J4") (pin "B7") (pinfunction "DN2_B7") (pintype "bidirectional"))
    )
    (net (code "9") (name "DP") (class "Default")
      (node (ref "D3") (pin "3") (pinfunction "I/O2_1_3") (pintype "bidirectional"))
      (node (ref "J4") (pin "A6") (pinfunction "DP1_A6") (pintype "bidirectional"))
      (node (ref "J4") (pin "B6") (pinfunction "DP2_B6") (pintype "bidirectional"))
    )
    (net (code "10") (name "EPD_3V3") (class "Default")
      (node (ref "C1-EP-DR") (pin "1") (pinfunction "1_1") (pintype "passive"))
      (node (ref "EPD_C5") (pin "2") (pinfunction "2_2") (pintype "passive"))
      (node (ref "J1") (pin "15") (pinfunction "15_15") (pintype "bidirectional"))
      (node (ref "J1") (pin "16") (pinfunction "16_16") (pintype "bidirectional"))
      (node (ref "L5") (pin "2") (pinfunction "2_2") (pintype "passive"))
      (node (ref "Q1") (pin "3") (pinfunction "D_3") (pintype "bidirectional"))
    )
    (net (code "11") (name "EPD_BUSY") (class "Default")
      (node (ref "J1") (pin "9") (pinfunction "9_9") (pintype "bidirectional"))
      (node (ref "U1") (pin "P$AD12") (pinfunction "P0.17_P$AD12") (pintype "bidirectional"))
    )
    (net (code "12") (name "EPD_CS") (class "Default")
      (node (ref "J1") (pin "12") (pinfunction "12_12") (pintype "bidirectional"))
      (node (ref "U1") (pin "P$K2") (pinfunction "P0.05/AIN3_P$K2") (pintype "bidirectional"))
    )
    (net (code "13") (name "EPD_DC") (class "Default")
      (node (ref "J1") (pin "11") (pinfunction "11_11") (pintype "bidirectional"))
      (node (ref "U1") (pin "P$AD10") (pinfunction "P0.15_P$AD10") (pintype "bidirectional"))
    )
    (net (code "14") (name "EPD_RST") (class "Default")
      (node (ref "J1") (pin "10") (pinfunction "10_10") (pintype "bidirectional"))
      (node (ref "U1") (pin "P$AC11") (pinfunction "P0.16_P$AC11") (pintype "bidirectional"))
    )
    (net (code "15") (name "GDR") (class "Default")
      (node (ref "J1") (pin "2") (pinfunction "2_2") (pintype "bidirectional"))
      (node (ref "Q3") (pin "1") (pinfunction "G_1") (pintype "bidirectional"))
      (node (ref "R2_EP_DR1") (pin "2") (pinfunction "2_2") (pintype "bidirectional"))
    )
    (net (code "16") (name "GND") (class "Default")
      (node (ref "C1") (pin "2") (pinfunction "2_2") (pintype "passive"))
      (node (ref "C1-EP-DR") (pin "2") (pinfunction "2_2") (pintype "passive"))
      (node (ref "C10") (pin "2") (pinfunction "2_2") (pintype "passive"))
      (node (ref "C11") (pin "2") (pinfunction "2_2") (pintype "passive"))
      (node (ref "C12") (pin "2") (pinfunction "2_2") (pintype "passive"))
      (node (ref "C13") (pin "2") (pinfunction "2_2") (pintype "passive"))
      (node (ref "C14") (pin "2") (pinfunction "2_2") (pintype "passive"))
      (node (ref "C15") (pin "2") (pinfunction "2_2") (pintype "passive"))
      (node (ref "C16") (pin "2") (pinfunction "2_2") (pintype "passive"))
      (node (ref "C17") (pin "1") (pinfunction "1_1") (pintype "passive"))
      (node (ref "C18") (pin "1") (pinfunction "1_1") (pintype "passive"))
      (node (ref "C19") (pin "2") (pinfunction "2_2") (pintype "passive"))
      (node (ref "C2") (pin "2") (pinfunction "2_2") (pintype "passive"))
      (node (ref "C20") (pin "2") (pinfunction "2_2") (pintype "passive"))
      (node (ref "C21") (pin "2") (pinfunction "2_2") (pintype "passive"))
      (node (ref "C22") (pin "2") (pinfunction "2_2") (pintype "passive"))
      (node (ref "C23") (pin "1") (pinfunction "1_1") (pintype "passive"))
      (node (ref "C24") (pin "1") (pinfunction "1_1") (pintype "passive"))
      (node (ref "C25") (pin "2") (pinfunction "2_2") (pintype "passive"))
      (node (ref "C27") (pin "1") (pinfunction "1_1") (pintype "passive"))
      (node (ref "C29") (pin "1") (pinfunction "1_1") (pintype "passive"))
      (node (ref "C3") (pin "2") (pinfunction "2_2") (pintype "passive"))
      (node (ref "C30") (pin "1") (pinfunction "1_1") (pintype "passive"))
      (node (ref "C31") (pin "1") (pinfunction "1_1") (pintype "passive"))
      (node (ref "C32") (pin "1") (pinfunction "1_1") (pintype "passive"))
      (node (ref "C33") (pin "2") (pinfunction "2_2") (pintype "passive"))
      (node (ref "C34") (pin "1") (pinfunction "1_1") (pintype "passive"))
      (node (ref "C37") (pin "1") (pinfunction "1_1") (pintype "passive"))
      (node (ref "C38") (pin "1") (pinfunction "1_1") (pintype "passive"))
      (node (ref "C39") (pin "2") (pinfunction "2_2") (pintype "passive"))
      (node (ref "C4") (pin "2") (pinfunction "2_2") (pintype "passive"))
      (node (ref "C42") (pin "1") (pinfunction "1_1") (pintype "passive"))
      (node (ref "C43") (pin "2") (pinfunction "2_2") (pintype "passive"))
      (node (ref "C5") (pin "2") (pinfunction "2_2") (pintype "passive"))
      (node (ref "C6") (pin "2") (pinfunction "2_2") (pintype "passive"))
      (node (ref "C7") (pin "2") (pinfunction "2_2") (pintype "passive"))
      (node (ref "C8") (pin "2") (pinfunction "2_2") (pintype "passive"))
      (node (ref "C9") (pin "2") (pinfunction "2_2") (pintype "passive"))
      (node (ref "D3") (pin "2") (pinfunction "GND_2") (pintype "bidirectional"))
      (node (ref "D4") (pin "1") (pinfunction "K_1") (pintype "bidirectional"))
      (node (ref "EPD_C1") (pin "1") (pinfunction "1_1") (pintype "passive"))
      (node (ref "EPD_C10") (pin "1") (pinfunction "1_1") (pintype "passive"))
      (node (ref "EPD_C11") (pin "1") (pinfunction "1_1") (pintype "passive"))
      (node (ref "EPD_C12") (pin "1") (pinfunction "1_1") (pintype "passive"))
      (node (ref "EPD_C2") (pin "1") (pinfunction "1_1") (pintype "passive"))
      (node (ref "EPD_C5") (pin "1") (pinfunction "1_1") (pintype "passive"))
      (node (ref "EPD_C6") (pin "1") (pinfunction "1_1") (pintype "passive"))
      (node (ref "EPD_C7") (pin "1") (pinfunction "1_1") (pintype "passive"))
      (node (ref "EPD_C8") (pin "1") (pinfunction "1_1") (pintype "passive"))
      (node (ref "EPD_C9") (pin "1") (pinfunction "1_1") (pintype "passive"))
      (node (ref "IC1") (pin "D2") (pinfunction "GND_D2") (pintype "bidirectional"))
      (node (ref "IC2") (pin "B1") (pinfunction "IN/TRIG_B1") (pintype "bidirectional"))
      (node (ref "IC2") (pin "B3") (pinfunction "GND_B3") (pintype "bidirectional"))
      (node (ref "IC3") (pin "8") (pinfunction "GNDIO_8") (pintype "bidirectional"))
      (node (ref "IC3") (pin "9") (pinfunction "GND_9") (pintype "bidirectional"))
      (node (ref "IC9") (pin "B1") (pinfunction "VSEL_B1") (pintype "bidirectional"))
      (node (ref "IC9") (pin "C1") (pinfunction "AGND_C1") (pintype "bidirectional"))
      (node (ref "IC9") (pin "C2") (pinfunction "PGND_1_C2") (pintype "bidirectional"))
      (node (ref "IC9") (pin "C3") (pinfunction "PGND_2_C3") (pintype "bidirectional"))
      (node (ref "J1") (pin "17") (pinfunction "17_17") (pintype "bidirectional"))
      (node (ref "J1") (pin "8") (pinfunction "8_8") (pintype "bidirectional"))
      (node (ref "J1") (pin "MP1") (pinfunction "MP1_MP1") (pintype "bidirectional"))
      (node (ref "J1") (pin "MP2") (pinfunction "MP2_MP2") (pintype "bidirectional"))
      (node (ref "J2") (pin "3") (pinfunction "3_3") (pintype "bidirectional"))
      (node (ref "J2") (pin "5") (pinfunction "5_5") (pintype "bidirectional"))
      (node (ref "J4") (pin "A12_B1") (pinfunction "GND_A12_B1") (pintype "power_in"))
      (node (ref "J4") (pin "A1_B12") (pinfunction "GND_A1_B12") (pintype "power_in"))
      (node (ref "J4") (pin "SH1") (pinfunction "SHIELD_SH1") (pintype "passive"))
      (node (ref "J4") (pin "SH2") (pinfunction "SHIELD_SH2") (pintype "passive"))
      (node (ref "J4") (pin "SH3") (pinfunction "SHIELD_SH3") (pintype "passive"))
      (node (ref "J4") (pin "SH4") (pinfunction "SHIELD_SH4") (pintype "passive"))
      (node (ref "R1_USB") (pin "1") (pinfunction "1_1") (pintype "bidirectional"))
      (node (ref "R2_EP_DR1") (pin "1") (pinfunction "1_1") (pintype "bidirectional"))
      (node (ref "R2_USB") (pin "2") (pinfunction "2_2") (pintype "bidirectional"))
      (node (ref "R3") (pin "1") (pinfunction "1_1") (pintype "bidirectional"))
      (node (ref "R9") (pin "1") (pinfunction "1_1") (pintype "bidirectional"))
      (node (ref "R_TYPE_SEL") (pin "1") (pinfunction "1_1") (pintype "bidirectional"))
      (node (ref "SJ1") (pin "1") (pinfunction "1_1") (pintype "passive"))
      (node (ref "SW_DN") (pin "1") (pinfunction "1_1") (pintype "passive"))
      (node (ref "SW_ENT") (pin "1") (pinfunction "1_1") (pintype "passive"))
      (node (ref "SW_UP") (pin "1") (pinfunction "1_1") (pintype "passive"))
      (node (ref "TP_BAT_GND") (pin "TP") (pinfunction "TP_TP") (pintype "input"))
      (node (ref "TP_GND") (pin "TP") (pinfunction "TP_TP") (pintype "input"))
      (node (ref "U1") (pin "P$74") (pinfunction "VSS_PAD_P$74") (pintype "bidirectional"))
      (node (ref "U1") (pin "P$75") (pinfunction "VSS_PAD_P$75") (pintype "bidirectional"))
      (node (ref "U1") (pin "P$76") (pinfunction "VSS_PAD_P$76") (pintype "bidirectional"))
      (node (ref "U1") (pin "P$77") (pinfunction "VSS_PAD_P$77") (pintype "bidirectional"))
      (node (ref "U1") (pin "P$78") (pinfunction "VSS_PAD_P$78") (pintype "bidirectional"))
      (node (ref "U1") (pin "P$79") (pinfunction "VSS_PAD_P$79") (pintype "bidirectional"))
      (node (ref "U1") (pin "P$80") (pinfunction "VSS_PAD_P$80") (pintype "bidirectional"))
      (node (ref "U1") (pin "P$81") (pinfunction "VSS_PAD_P$81") (pintype "bidirectional"))
      (node (ref "U1") (pin "P$82") (pinfunction "VSS_PAD_P$82") (pintype "bidirectional"))
      (node (ref "U1") (pin "P$83") (pinfunction "VSS_PAD_P$83") (pintype "bidirectional"))
      (node (ref "U1") (pin "P$84") (pinfunction "VSS_PAD_P$84") (pintype "bidirectional"))
      (node (ref "U1") (pin "P$85") (pinfunction "VSS_PAD_P$85") (pintype "bidirectional"))
      (node (ref "U1") (pin "P$86") (pinfunction "VSS_PAD_P$86") (pintype "bidirectional"))
      (node (ref "U1") (pin "P$87") (pinfunction "VSS_PAD_P$87") (pintype "bidirectional"))
      (node (ref "U1") (pin "P$88") (pinfunction "VSS_PAD_P$88") (pintype "bidirectional"))
      (node (ref "U1") (pin "P$89") (pinfunction "VSS_PAD_P$89") (pintype "bidirectional"))
      (node (ref "U1") (pin "P$90") (pinfunction "VSS_PAD_P$90") (pintype "bidirectional"))
      (node (ref "U1") (pin "P$B7") (pinfunction "VSS_P$B7") (pintype "power_in"))
      (node (ref "U1") (pin "P$F23") (pinfunction "VSS_PA_P$F23") (pintype "bidirectional"))
      (node (ref "U3") (pin "1") (pinfunction "CTG_1") (pintype "power_in"))
      (node (ref "U3") (pin "4") (pinfunction "GND_4") (pintype "power_in"))
      (node (ref "U3") (pin "6") (pinfunction "QSTRT_6") (pintype "input"))
      (node (ref "U3") (pin "9") (pinfunction "EP_9") (pintype "power_in"))
      (node (ref "X1") (pin "2") (pinfunction "2_2") (pintype "passive"))
      (node (ref "X1") (pin "4") (pinfunction "4_4") (pintype "passive"))
    )
    (net (code "17") (name "HAPTIC_EN") (class "Default")
      (node (ref "IC2") (pin "A1") (pinfunction "EN_A1") (pintype "bidirectional"))
      (node (ref "U1") (pin "P$U1") (pinfunction "P0.12_P$U1") (pintype "bidirectional"))
    )
    (net (code "18") (name "IMU_INT1") (class "Default")
      (node (ref "IC3") (pin "5") (pinfunction "INT1_5") (pintype "bidirectional"))
      (node (ref "U1") (pin "P$N1") (pinfunction "P0.08_P$N1") (pintype "bidirectional"))
    )
    (net (code "19") (name "IMU_INT2") (class "Default")
      (node (ref "IC3") (pin "6") (pinfunction "INT2_6") (pintype "bidirectional"))
      (node (ref "U1") (pin "P$P2") (pinfunction "P1.08_P$P2") (pintype "bidirectional"))
    )
    (net (code "20") (name "LX1") (class "Default")
      (node (ref "IC9") (pin "B2") (pinfunction "SW1_1_B2") (pintype "bidirectional"))
      (node (ref "IC9") (pin "B3") (pinfunction "SW1_2_B3") (pintype "bidirectional"))
      (node (ref "L7") (pin "1") (pinfunction "1_1") (pintype "bidirectional"))
    )
    (net (code "21") (name "LX2") (class "Default")
      (node (ref "IC9") (pin "D2") (pinfunction "SW2_1_D2") (pintype "bidirectional"))
      (node (ref "IC9") (pin "D3") (pinfunction "SW2_2_D3") (pintype "bidirectional"))
      (node (ref "L7") (pin "2") (pinfunction "2_2") (pintype "bidirectional"))
    )
    (net (code "22") (name "MOSI") (class "Default")
      (node (ref "J1") (pin "14") (pinfunction "14_14") (pintype "bidirectional"))
      (node (ref "U1") (pin "P$B13") (pinfunction "P0.03/AIN1_P$B13") (pintype "bidirectional"))
    )
    (net (code "23") (name "Net-(D2-K)") (class "Default")
      (node (ref "C2-EP-DR") (pin "1") (pinfunction "1_1") (pintype "passive"))
      (node (ref "D2") (pin "1") (pinfunction "K_1") (pintype "bidirectional"))
      (node (ref "D4") (pin "2") (pinfunction "A_2") (pintype "bidirectional"))
      (node (ref "Q3") (pin "3") (pinfunction "D_3") (pintype "bidirectional"))
    )
    (net (code "24") (name "Net-(D5-A)") (class "Default")
      (node (ref "C2-EP-DR") (pin "2") (pinfunction "2_2") (pintype "passive"))
      (node (ref "D5") (pin "2") (pinfunction "A_2") (pintype "bidirectional"))
      (node (ref "L5") (pin "1") (pinfunction "1_1") (pintype "passive"))
    )
    (net (code "25") (name "Net-(EPD_C1-Pad2)") (class "Default")
      (node (ref "EPD_C1") (pin "2") (pinfunction "2_2") (pintype "passive"))
      (node (ref "J1") (pin "5") (pinfunction "5_5") (pintype "bidirectional"))
    )
    (net (code "26") (name "Net-(EPD_C2-Pad2)") (class "Default")
      (node (ref "EPD_C2") (pin "2") (pinfunction "2_2") (pintype "passive"))
      (node (ref "J1") (pin "4") (pinfunction "4_4") (pintype "bidirectional"))
    )
    (net (code "27") (name "Net-(EPD_C6-Pad2)") (class "Default")
      (node (ref "EPD_C6") (pin "2") (pinfunction "2_2") (pintype "passive"))
      (node (ref "J1") (pin "18") (pinfunction "18_18") (pintype "bidirectional"))
    )
    (net (code "28") (name "Net-(EPD_C7-Pad2)") (class "Default")
      (node (ref "EPD_C7") (pin "2") (pinfunction "2_2") (pintype "passive"))
      (node (ref "J1") (pin "19") (pinfunction "19_19") (pintype "bidirectional"))
    )
    (net (code "29") (name "Net-(EPD_C8-Pad2)") (class "Default")
      (node (ref "EPD_C8") (pin "2") (pinfunction "2_2") (pintype "passive"))
      (node (ref "J1") (pin "20") (pinfunction "20_20") (pintype "bidirectional"))
    )
    (net (code "30") (name "Net-(EPD_C10-Pad2)") (class "Default")
      (node (ref "EPD_C10") (pin "2") (pinfunction "2_2") (pintype "passive"))
      (node (ref "J1") (pin "22") (pinfunction "22_22") (pintype "bidirectional"))
    )
    (net (code "31") (name "Net-(EPD_C12-Pad2)") (class "Default")
      (node (ref "EPD_C12") (pin "2") (pinfunction "2_2") (pintype "passive"))
      (node (ref "J1") (pin "24") (pinfunction "24_24") (pintype "bidirectional"))
    )
    (net (code "32") (name "Net-(IC1-TS{slash}MR)") (class "Default")
      (node (ref "IC1") (pin "D1") (pinfunction "TS/MR_D1") (pintype "bidirectional"))
      (node (ref "R9") (pin "2") (pinfunction "2_2") (pintype "bidirectional"))
    )
    (net (code "33") (name "Net-(IC2-REG)") (class "Default")
      (node (ref "C32") (pin "2") (pinfunction "2_2") (pintype "passive"))
      (node (ref "IC2") (pin "A2") (pinfunction "REG_A2") (pintype "bidirectional"))
    )
    (net (code "34") (name "Net-(IC3-SDO)") (class "Default")
      (node (ref "IC3") (pin "1") (pinfunction "SDO_1") (pintype "bidirectional"))
      (node (ref "R3") (pin "2") (pinfunction "2_2") (pintype "bidirectional"))
    )
    (net (code "35") (name "Net-(IC9-SCL)") (class "Default")
      (node (ref "IC9") (pin "D1") (pinfunction "SCL_D1") (pintype "bidirectional"))
      (node (ref "R4") (pin "2") (pinfunction "2_2") (pintype "bidirectional"))
    )
    (net (code "36") (name "Net-(IC9-SDA)") (class "Default")
      (node (ref "IC9") (pin "E1") (pinfunction "SDA_E1") (pintype "bidirectional"))
      (node (ref "R2") (pin "2") (pinfunction "2_2") (pintype "bidirectional"))
    )
    (net (code "37") (name "Net-(J4-CC1)") (class "Default")
      (node (ref "J4") (pin "A5") (pinfunction "CC1_A5") (pintype "bidirectional"))
      (node (ref "R1_USB") (pin "2") (pinfunction "2_2") (pintype "bidirectional"))
    )
    (net (code "38") (name "Net-(J4-CC2)") (class "Default")
      (node (ref "J4") (pin "B5") (pinfunction "CC2_B5") (pintype "bidirectional"))
      (node (ref "R2_USB") (pin "1") (pinfunction "1_1") (pintype "bidirectional"))
    )
    (net (code "39") (name "Net-(L2-Pad2)") (class "Default")
      (node (ref "L2") (pin "2") (pinfunction "2_2") (pintype "passive"))
      (node (ref "L3") (pin "1") (pinfunction "1_1") (pintype "passive"))
    )
    (net (code "40") (name "Net-(R1_EP_DR-Pad1)") (class "Default")
      (node (ref "R1_EP_DR") (pin "1") (pinfunction "1_1") (pintype "bidirectional"))
      (node (ref "R_TYPE_SEL") (pin "2") (pinfunction "2_2") (pintype "bidirectional"))
      (node (ref "SJ1") (pin "2") (pinfunction "2_2") (pintype "passive"))
    )
    (net (code "41") (name "Net-(U1-ANT)") (class "Default")
      (node (ref "C3") (pin "1") (pinfunction "1_1") (pintype "passive"))
      (node (ref "L1") (pin "1") (pinfunction "1_1") (pintype "passive"))
      (node (ref "U1") (pin "P$H23") (pinfunction "ANT_P$H23") (pintype "bidirectional"))
    )
    (net (code "42") (name "Net-(U1-DCC)") (class "Default")
      (node (ref "L2") (pin "1") (pinfunction "1_1") (pintype "passive"))
      (node (ref "U1") (pin "P$B3") (pinfunction "DCC_P$B3") (pintype "output"))
    )
    (net (code "43") (name "Net-(U1-DEC2)") (class "Default")
      (node (ref "C13") (pin "1") (pinfunction "1_1") (pintype "passive"))
      (node (ref "U1") (pin "P$A18") (pinfunction "DEC2_P$A18") (pintype "bidirectional"))
    )
    (net (code "44") (name "Net-(U1-DEC3)") (class "Default")
      (node (ref "C11") (pin "1") (pinfunction "1_1") (pintype "passive"))
      (node (ref "U1") (pin "P$D23") (pinfunction "DEC3_P$D23") (pintype "bidirectional"))
    )
    (net (code "45") (name "Net-(U1-DEC3V3)") (class "Default")
      (node (ref "C20") (pin "1") (pinfunction "1_1") (pintype "passive"))
      (node (ref "U1") (pin "P$AC5") (pinfunction "DEC3V3_P$AC5") (pintype "bidirectional"))
    )
    (net (code "46") (name "Net-(U1-DEC5)") (class "Default")
      (node (ref "C9") (pin "1") (pinfunction "1_1") (pintype "passive"))
      (node (ref "U1") (pin "P$N24") (pinfunction "DEC5_P$N24") (pintype "bidirectional"))
    )
    (net (code "47") (name "Net-(U1-XC1)") (class "Default")
      (node (ref "C1") (pin "1") (pinfunction "1_1") (pintype "passive"))
      (node (ref "U1") (pin "P$B24") (pinfunction "XC1_P$B24") (pintype "input"))
      (node (ref "X1") (pin "1") (pinfunction "1_1") (pintype "passive"))
    )
    (net (code "48") (name "Net-(U1-XC2)") (class "Default")
      (node (ref "C2") (pin "1") (pinfunction "1_1") (pintype "passive"))
      (node (ref "U1") (pin "P$A23") (pinfunction "XC2_P$A23") (pintype "output"))
      (node (ref "X1") (pin "3") (pinfunction "3_3") (pintype "passive"))
    )
    (net (code "49") (name "OUT+") (class "Default")
      (node (ref "IC2") (pin "A3") (pinfunction "OUT+_A3") (pintype "bidirectional"))
      (node (ref "TP_OP") (pin "TP") (pinfunction "TP_TP") (pintype "input"))
    )
    (net (code "50") (name "OUT-") (class "Default")
      (node (ref "IC2") (pin "C3") (pinfunction "OUT-_C3") (pintype "bidirectional"))
      (node (ref "TP_ON") (pin "TP") (pinfunction "TP_TP") (pintype "input"))
    )
    (net (code "51") (name "P0.00{slash}XL1") (class "Default")
      (node (ref "C17") (pin "2") (pinfunction "2_2") (pintype "passive"))
      (node (ref "U1") (pin "P$D2") (pinfunction "P0.00/XL1_P$D2") (pintype "bidirectional"))
      (node (ref "X2") (pin "1") (pinfunction "1_1") (pintype "passive"))
    )
    (net (code "52") (name "P0.01{slash}XL2") (class "Default")
      (node (ref "C18") (pin "2") (pinfunction "2_2") (pintype "passive"))
      (node (ref "U1") (pin "P$F2") (pinfunction "P0.01/XL2_P$F2") (pintype "bidirectional"))
      (node (ref "X2") (pin "2") (pinfunction "2_2") (pintype "passive"))
    )
    (net (code "53") (name "P0.04") (class "Default")
      (node (ref "U1") (pin "P$J1") (pinfunction "P0.04/AIN2_P$J1") (pintype "bidirectional"))
    )
    (net (code "54") (name "P0.09") (class "Default")
      (node (ref "U1") (pin "P$L24") (pinfunction "P0.09/NFC1_P$L24") (pintype "bidirectional"))
    )
    (net (code "55") (name "P0.13") (class "Default")
      (node (ref "C30") (pin "2") (pinfunction "2_2") (pintype "passive"))
      (node (ref "R5") (pin "1") (pinfunction "1_1") (pintype "bidirectional"))
      (node (ref "SW_UP") (pin "2") (pinfunction "2_2") (pintype "passive"))
      (node (ref "U1") (pin "P$AD8") (pinfunction "P0.13_P$AD8") (pintype "bidirectional"))
    )
    (net (code "56") (name "P0.14") (class "Default")
      (node (ref "C31") (pin "2") (pinfunction "2_2") (pintype "passive"))
      (node (ref "R8") (pin "1") (pinfunction "1_1") (pintype "bidirectional"))
      (node (ref "SW_ENT") (pin "2") (pinfunction "2_2") (pintype "passive"))
      (node (ref "U1") (pin "P$AC9") (pinfunction "P0.14_P$AC9") (pintype "bidirectional"))
    )
    (net (code "57") (name "P0.19") (class "Default")
      (node (ref "U1") (pin "P$AC15") (pinfunction "P0.19_P$AC15") (pintype "bidirectional"))
    )
    (net (code "58") (name "P0.20") (class "Default")
      (node (ref "U1") (pin "P$AD16") (pinfunction "P0.20_P$AD16") (pintype "bidirectional"))
    )
    (net (code "59") (name "P0.21") (class "Default")
      (node (ref "U1") (pin "P$AC17") (pinfunction "P0.21_P$AC17") (pintype "bidirectional"))
    )
    (net (code "60") (name "P0.22") (class "Default")
      (node (ref "U1") (pin "P$AD18") (pinfunction "P0.22_P$AD18") (pintype "bidirectional"))
    )
    (net (code "61") (name "P0.23") (class "Default")
      (node (ref "U1") (pin "P$AC19") (pinfunction "P0.23_P$AC19") (pintype "bidirectional"))
    )
    (net (code "62") (name "P0.24") (class "Default")
      (node (ref "U1") (pin "P$AD20") (pinfunction "P0.24_P$AD20") (pintype "bidirectional"))
    )
    (net (code "63") (name "P0.25") (class "Default")
      (node (ref "U1") (pin "P$AC21") (pinfunction "P0.25_P$AC21") (pintype "bidirectional"))
    )
    (net (code "64") (name "P0.26") (class "Default")
      (node (ref "U1") (pin "P$G1") (pinfunction "P0.26_P$G1") (pintype "bidirectional"))
    )
    (net (code "65") (name "P0.27") (class "Default")
      (node (ref "U1") (pin "P$H2") (pinfunction "P0.27_P$H2") (pintype "bidirectional"))
    )
    (net (code "66") (name "P0.28") (class "Default")
      (node (ref "U1") (pin "P$B11") (pinfunction "P0.28/AIN4_P$B11") (pintype "bidirectional"))
    )
    (net (code "67") (name "P0.29") (class "Default")
      (node (ref "U1") (pin "P$A10") (pinfunction "P0.29/AIN5_P$A10") (pintype "bidirectional"))
    )
    (net (code "68") (name "P0.30") (class "Default")
      (node (ref "U1") (pin "P$B9") (pinfunction "P0.30/AIN6_P$B9") (pintype "bidirectional"))
    )
    (net (code "69") (name "P0.31") (class "Default")
      (node (ref "U1") (pin "P$A8") (pinfunction "P0.31/AIN7_P$A8") (pintype "bidirectional"))
    )
    (net (code "70") (name "P1.01") (class "Default")
      (node (ref "Q1") (pin "1") (pinfunction "G_1") (pintype "bidirectional"))
      (node (ref "R_PWR_EPD") (pin "1") (pinfunction "1_1") (pintype "bidirectional"))
      (node (ref "U1") (pin "P$Y23") (pinfunction "P1.01_P$Y23") (pintype "bidirectional"))
    )
    (net (code "71") (name "P1.02") (class "Default")
      (node (ref "C29") (pin "2") (pinfunction "2_2") (pintype "passive"))
      (node (ref "R7") (pin "1") (pinfunction "1_1") (pintype "bidirectional"))
      (node (ref "SW_DN") (pin "2") (pinfunction "2_2") (pintype "passive"))
      (node (ref "U1") (pin "P$W24") (pinfunction "P1.02_P$W24") (pintype "bidirectional"))
    )
    (net (code "72") (name "P1.03") (class "Default")
      (node (ref "U1") (pin "P$V23") (pinfunction "P1.03_P$V23") (pintype "bidirectional"))
    )
    (net (code "73") (name "P1.04") (class "Default")
      (node (ref "U1") (pin "P$U24") (pinfunction "P1.04_P$U24") (pintype "bidirectional"))
    )
    (net (code "74") (name "P1.05") (class "Default")
      (node (ref "U1") (pin "P$T23") (pinfunction "P1.05_P$T23") (pintype "bidirectional"))
    )
    (net (code "75") (name "P1.06") (class "Default")
      (node (ref "U1") (pin "P$R24") (pinfunction "P1.06_P$R24") (pintype "bidirectional"))
    )
    (net (code "76") (name "P1.07") (class "Default")
      (node (ref "U1") (pin "P$P23") (pinfunction "P1.07_P$P23") (pintype "bidirectional"))
    )
    (net (code "77") (name "P1.09") (class "Default")
      (node (ref "U1") (pin "P$R1") (pinfunction "P1.09_P$R1") (pintype "bidirectional"))
    )
    (net (code "78") (name "P1.10") (class "Default")
      (node (ref "U1") (pin "P$A20") (pinfunction "P1.10_P$A20") (pintype "bidirectional"))
    )
    (net (code "79") (name "P1.11") (class "Default")
      (node (ref "U1") (pin "P$B19") (pinfunction "P1.11_P$B19") (pintype "bidirectional"))
    )
    (net (code "80") (name "P1.12") (class "Default")
      (node (ref "U1") (pin "P$B17") (pinfunction "P1.12_P$B17") (pintype "bidirectional"))
    )
    (net (code "81") (name "P1.13") (class "Default")
      (node (ref "U1") (pin "P$A16") (pinfunction "P1.13_P$A16") (pintype "bidirectional"))
    )
    (net (code "82") (name "P1.14") (class "Default")
      (node (ref "U1") (pin "P$B15") (pinfunction "P1.14_P$B15") (pintype "bidirectional"))
    )
    (net (code "83") (name "P1.15") (class "Default")
      (node (ref "U1") (pin "P$A14") (pinfunction "P1.15_P$A14") (pintype "bidirectional"))
    )
    (net (code "84") (name "PMIC_INT") (class "Default")
      (node (ref "IC1") (pin "A1") (pinfunction "~{INT}_A1") (pintype "bidirectional"))
      (node (ref "U1") (pin "P$T2") (pinfunction "P0.11_P$T2") (pintype "bidirectional"))
    )
    (net (code "85") (name "PREVGH") (class "Default")
      (node (ref "D5") (pin "1") (pinfunction "K_1") (pintype "bidirectional"))
      (node (ref "EPD_C9") (pin "2") (pinfunction "2_2") (pintype "passive"))
      (node (ref "J1") (pin "21") (pinfunction "21_21") (pintype "bidirectional"))
    )
    (net (code "86") (name "PREVGL") (class "Default")
      (node (ref "D2") (pin "2") (pinfunction "A_2") (pintype "bidirectional"))
      (node (ref "EPD_C11") (pin "2") (pinfunction "2_2") (pintype "passive"))
      (node (ref "J1") (pin "23") (pinfunction "23_23") (pintype "bidirectional"))
    )
    (net (code "87") (name "RESE") (class "Default")
      (node (ref "J1") (pin "3") (pinfunction "3_3") (pintype "bidirectional"))
      (node (ref "Q3") (pin "2") (pinfunction "S_2") (pintype "bidirectional"))
      (node (ref "R1_EP_DR") (pin "2") (pinfunction "2_2") (pintype "bidirectional"))
    )
    (net (code "88") (name "RESET") (class "Default")
      (node (ref "J2") (pin "6") (pinfunction "6_6") (pintype "bidirectional"))
      (node (ref "TP_RESET") (pin "TP") (pinfunction "TP_TP") (pintype "input"))
      (node (ref "U1") (pin "P$AC13") (pinfunction "P0.18/RESET_P$AC13") (pintype "bidirectional"))
    )
    (net (code "89") (name "RF") (class "Default")
      (node (ref "ANT1") (pin "1") (pinfunction "FEED_1") (pintype "input"))
      (node (ref "C22") (pin "1") (pinfunction "1_1") (pintype "passive"))
      (node (ref "C4") (pin "1") (pinfunction "1_1") (pintype "passive"))
      (node (ref "L1") (pin "2") (pinfunction "2_2") (pintype "passive"))
    )
    (net (code "90") (name "SCK") (class "Default")
      (node (ref "J1") (pin "13") (pinfunction "13_13") (pintype "bidirectional"))
      (node (ref "U1") (pin "P$A12") (pinfunction "P0.02/AIN0_P$A12") (pintype "bidirectional"))
    )
    (net (code "91") (name "SCL") (class "Default")
      (node (ref "IC1") (pin "B1") (pinfunction "SCL_B1") (pintype "bidirectional"))
      (node (ref "IC2") (pin "C1") (pinfunction "SCL_C1") (pintype "bidirectional"))
      (node (ref "IC3") (pin "12") (pinfunction "SCX_12") (pintype "bidirectional"))
      (node (ref "R17") (pin "2") (pinfunction "2_2") (pintype "bidirectional"))
      (node (ref "R4") (pin "1") (pinfunction "1_1") (pintype "bidirectional"))
      (node (ref "TP_SCL") (pin "TP") (pinfunction "TP_TP") (pintype "input"))
      (node (ref "U1") (pin "P$M2") (pinfunction "P0.07_P$M2") (pintype "bidirectional"))
      (node (ref "U3") (pin "7") (pinfunction "SCL_7") (pintype "input"))
    )
    (net (code "92") (name "SDA") (class "Default")
      (node (ref "IC1") (pin "C1") (pinfunction "SDA_C1") (pintype "bidirectional"))
      (node (ref "IC2") (pin "B2") (pinfunction "SDA_B2") (pintype "bidirectional"))
      (node (ref "IC3") (pin "2") (pinfunction "SDX_2") (pintype "bidirectional"))
      (node (ref "R18") (pin "2") (pinfunction "2_2") (pintype "bidirectional"))
      (node (ref "R2") (pin "1") (pinfunction "1_1") (pintype "bidirectional"))
      (node (ref "TP_SDA") (pin "TP") (pinfunction "TP_TP") (pintype "input"))
      (node (ref "U1") (pin "P$L1") (pinfunction "P0.06_P$L1") (pintype "bidirectional"))
      (node (ref "U3") (pin "8") (pinfunction "SDA_8") (pintype "bidirectional"))
    )
    (net (code "93") (name "SWDCLK") (class "Default")
      (node (ref "J2") (pin "4") (pinfunction "4_4") (pintype "bidirectional"))
      (node (ref "TP_SWDCLK") (pin "TP") (pinfunction "TP_TP") (pintype "input"))
      (node (ref "U1") (pin "P$AA24") (pinfunction "SWDCLK_P$AA24") (pintype "input"))
    )
    (net (code "94") (name "SWDIO") (class "Default")
      (node (ref "J2") (pin "2") (pinfunction "2_2") (pintype "bidirectional"))
      (node (ref "TP_SWDIO") (pin "TP") (pinfunction "TP_TP") (pintype "input"))
      (node (ref "U1") (pin "P$AC24") (pinfunction "SWDIO_P$AC24") (pintype "bidirectional"))
    )
    (net (code "95") (name "SWO") (class "Default")
      (node (ref "TP_SWO") (pin "TP") (pinfunction "TP_TP") (pintype "input"))
      (node (ref "U1") (pin "P$AD22") (pinfunction "P1.00_P$AD22") (pintype "bidirectional"))
    )
    (net (code "96") (name "VBAT") (class "Default")
      (node (ref "C27") (pin "2") (pinfunction "2_2") (pintype "passive"))
      (node (ref "C37") (pin "2") (pinfunction "2_2") (pintype "passive"))
      (node (ref "IC1") (pin "C2") (pinfunction "BAT_C2") (pintype "bidirectional"))
      (node (ref "TP_VBAT") (pin "TP") (pinfunction "TP_TP") (pintype "input"))
      (node (ref "U3") (pin "2") (pinfunction "CELL_2") (pintype "power_in"))
      (node (ref "U3") (pin "3") (pinfunction "VDD_3") (pintype "power_in"))
    )
    (net (code "97") (name "VBUS") (class "Default")
      (node (ref "C21") (pin "1") (pinfunction "1_1") (pintype "passive"))
      (node (ref "C38") (pin "2") (pinfunction "2_2") (pintype "passive"))
      (node (ref "C42") (pin "2") (pinfunction "2_2") (pintype "passive"))
      (node (ref "C43") (pin "1") (pinfunction "1_1") (pintype "passive"))
      (node (ref "D3") (pin "5") (pinfunction "VBUS_5") (pintype "bidirectional"))
      (node (ref "IC1") (pin "A2") (pinfunction "IN_A2") (pintype "bidirectional"))
      (node (ref "J4") (pin "A4_B9") (pinfunction "VBUS_A4_B9") (pintype "power_in"))
      (node (ref "J4") (pin "A9_B4") (pinfunction "VBUS_A9_B4") (pintype "power_in"))
      (node (ref "U1") (pin "P$AD2") (pinfunction "VBUS_P$AD2") (pintype "power_in"))
    )
    (net (code "98") (name "VREG") (class "Default")
      (node (ref "C23") (pin "2") (pinfunction "2_2") (pintype "passive"))
      (node (ref "C24") (pin "2") (pinfunction "2_2") (pintype "passive"))
      (node (ref "C39") (pin "1") (pinfunction "1_1") (pintype "passive"))
      (node (ref "IC1") (pin "B2") (pinfunction "SYS_B2") (pintype "bidirectional"))
      (node (ref "IC9") (pin "A1") (pinfunction "EN_A1") (pintype "bidirectional"))
      (node (ref "IC9") (pin "A2") (pinfunction "VIN_1_A2") (pintype "bidirectional"))
      (node (ref "IC9") (pin "A3") (pinfunction "VIN_2_A3") (pintype "bidirectional"))
      (node (ref "TP_VREG") (pin "TP") (pinfunction "TP_TP") (pintype "input"))
    )
    (net (code "99") (name "unconnected-(ANT1-NC-Pad2)") (class "Default")
      (node (ref "ANT1") (pin "2") (pinfunction "NC_2") (pintype "no_connect"))
    )
    (net (code "100") (name "unconnected-(IC3-ASCL-Pad11)") (class "Default")
      (node (ref "IC3") (pin "11") (pinfunction "ASCL_11") (pintype "bidirectional"))
    )
    (net (code "101") (name "unconnected-(IC3-ASDA-Pad4)") (class "Default")
      (node (ref "IC3") (pin "4") (pinfunction "ASDA_4") (pintype "bidirectional"))
    )
    (net (code "102") (name "unconnected-(J1-Pad1)") (class "Default")
      (node (ref "J1") (pin "1") (pinfunction "1_1") (pintype "bidirectional"))
    )
    (net (code "103") (name "unconnected-(J1-Pad6)") (class "Default")
      (node (ref "J1") (pin "6") (pinfunction "6_6") (pintype "bidirectional"))
    )
    (net (code "104") (name "unconnected-(J1-Pad7)") (class "Default")
      (node (ref "J1") (pin "7") (pinfunction "7_7") (pintype "bidirectional"))
    )
    (net (code "105") (name "unconnected-(J4-SBU1-PadA8)") (class "Default")
      (node (ref "J4") (pin "A8") (pinfunction "SBU1_A8") (pintype "bidirectional"))
    )
    (net (code "106") (name "unconnected-(J4-SBU2-PadB8)") (class "Default")
      (node (ref "J4") (pin "B8") (pinfunction "SBU2_B8") (pintype "bidirectional"))
    )
    (net (code "107") (name "unconnected-(U1-DCCH-PadP$AB2)") (class "Default")
      (node (ref "U1") (pin "P$AB2") (pinfunction "DCCH_P$AB2") (pintype "bidirectional"))
    )
  )
)
